# AGC.net
KiCad netlist of a schematic drawn in Altium Designer
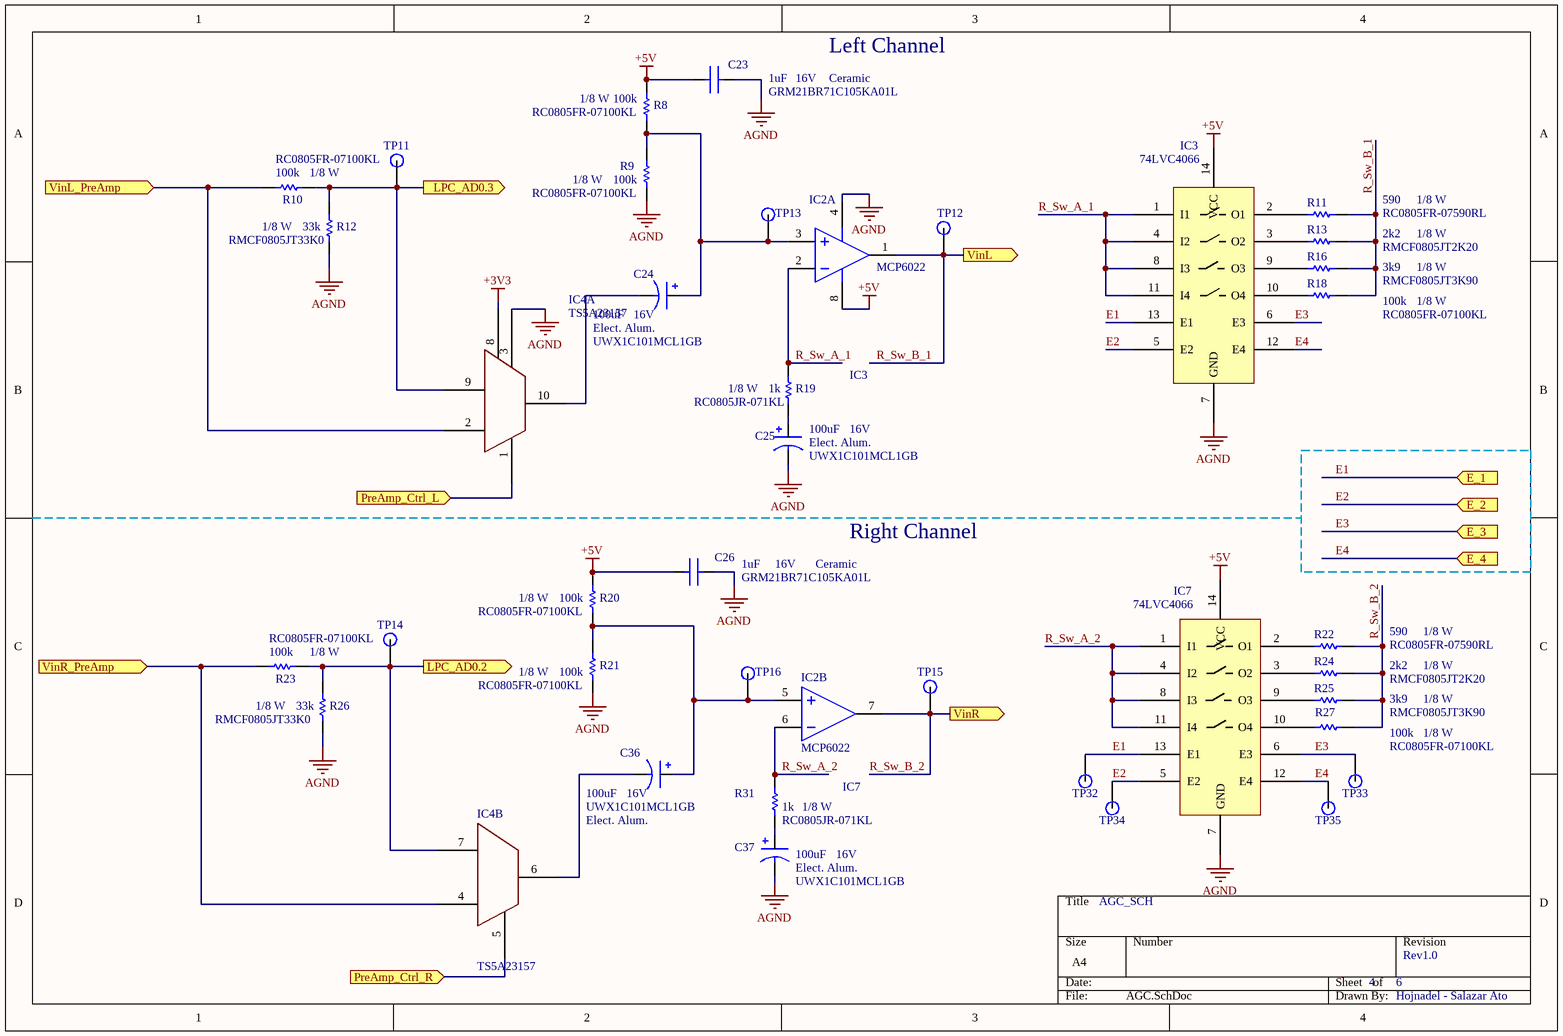
[diagram p0: AGC.SchDoc]

(export (version "E")
  (design (tool "Eeschema 10.0.6"))
  (components
    (comp (ref "C23")
      (value "1uF 16V Ceramic")
      (footprint "C_0805")
      (description "Capacitor")
      (fields
        (field (name "C") "1uF")
        (field (name "V") "16V")
        (field (name "PART NUMBER") "GRM21BR71C105KA01L")
        (field (name "MATERIAL") "Ceramic")
      )
      (libsource (lib "TDII_Lib_V2") (part "Cap1"))
    )
    (comp (ref "C24")
      (value "100uF 16V Elect. Alum.")
      (footprint "C_AE7066X54M")
      (description "Capacitor")
      (fields
        (field (name "C") "100uF")
        (field (name "V") "16V")
        (field (name "MATERIAL") "Elect. Alum.")
        (field (name "PART NUMBER") "UWX1C101MCL1GB")
      )
      (libsource (lib "TDII_Lib_V2") (part "Cap_Elec"))
    )
    (comp (ref "C25")
      (value "100uF 16V Elect. Alum.")
      (footprint "C_AE7066X54M")
      (description "Capacitor")
      (fields
        (field (name "C") "100uF")
        (field (name "V") "16V")
        (field (name "MATERIAL") "Elect. Alum.")
        (field (name "PART NUMBER") "UWX1C101MCL1GB")
      )
      (libsource (lib "") (part "Cap_Elec_1"))
    )
    (comp (ref "C26")
      (value "1uF 16V Ceramic")
      (footprint "C_0805")
      (description "Capacitor")
      (fields
        (field (name "C") "1uF")
        (field (name "V") "16V")
        (field (name "PART NUMBER") "GRM21BR71C105KA01L")
        (field (name "MATERIAL") "Ceramic")
      )
      (libsource (lib "TDII_Lib_V2") (part "Cap1"))
    )
    (comp (ref "C36")
      (value "100uF 16V Elect. Alum.")
      (footprint "C_AE7066X54M")
      (description "Capacitor")
      (fields
        (field (name "C") "100uF")
        (field (name "V") "16V")
        (field (name "MATERIAL") "Elect. Alum.")
        (field (name "PART NUMBER") "UWX1C101MCL1GB")
      )
      (libsource (lib "TDII_Lib_V2") (part "Cap_Elec"))
    )
    (comp (ref "C37")
      (value "100uF 16V Elect. Alum.")
      (footprint "C_AE7066X54M")
      (description "Capacitor")
      (fields
        (field (name "C") "100uF")
        (field (name "V") "16V")
        (field (name "MATERIAL") "Elect. Alum.")
        (field (name "PART NUMBER") "UWX1C101MCL1GB")
      )
      (libsource (lib "") (part "Cap_Elec_1"))
    )
    (comp (ref "IC2") (value "MCP6022") (footprint "SOIC_D8") (libsource (lib "LituLib") (part "OpAmp_Dual")))
    (comp (ref "IC3")
      (value "74LVC4066")
      (footprint "SO14")
      (fields (field (name "PART NUMBER") "74LVC4066BQ,115"))
      (libsource (lib "TDII_Lib_V2") (part "Q_B_Switch_2"))
    )
    (comp (ref "IC4")
      (value "TS5A23157")
      (footprint "TSSOP50P490X110-10N")
      (description "Analog Switch")
      (libsource (lib "TDII_Lib_V2") (part "A_SW_2x2{colon}1_VSSOP"))
    )
    (comp (ref "IC7")
      (value "74LVC4066")
      (footprint "SO14")
      (fields (field (name "PART NUMBER") "74LVC4066BQ,115"))
      (libsource (lib "TDII_Lib_V2") (part "Q_B_Switch_2"))
    )
    (comp (ref "R8")
      (value "100k")
      (footprint "R_0805")
      (description "Resistor")
      (fields
        (field (name "POWER") "1/8 W")
        (field (name "PART NUMBER") "RC0805FR-07100KL")
        (field (name "Comment") "100k 1/8W")
      )
      (libsource (lib "TDII_Lib_V2") (part "Res1"))
    )
    (comp (ref "R9")
      (value "100k")
      (footprint "R_0805")
      (description "Resistor")
      (fields
        (field (name "POWER") "1/8 W")
        (field (name "PART NUMBER") "RC0805FR-07100KL")
        (field (name "Comment") "100k 1/8W")
      )
      (libsource (lib "TDII_Lib_V2") (part "Res1"))
    )
    (comp (ref "R10")
      (value "100k")
      (footprint "R_0805")
      (description "Resistor")
      (fields
        (field (name "POWER") "1/8 W")
        (field (name "PART NUMBER") "RC0805FR-07100KL")
        (field (name "Comment") "100k 1/8W")
      )
      (libsource (lib "TDII_Lib_V2") (part "Res1"))
    )
    (comp (ref "R11")
      (value "590")
      (footprint "R_0805")
      (description "Resistor")
      (fields
        (field (name "POWER") "1/8 W")
        (field (name "PART NUMBER") "RC0805FR-07590RL")
        (field (name "Comment") "590 1/8W")
      )
      (libsource (lib "TDII_Lib_V2") (part "Res1"))
    )
    (comp (ref "R12")
      (value "33k")
      (footprint "R_0805")
      (description "Resistor")
      (fields
        (field (name "POWER") "1/8 W")
        (field (name "PART NUMBER") "RMCF0805JT33K0")
        (field (name "Comment") "33k 1/8W")
      )
      (libsource (lib "TDII_Lib_V2") (part "Res1"))
    )
    (comp (ref "R13")
      (value "2k2")
      (footprint "R_0805")
      (description "Resistor")
      (fields
        (field (name "POWER") "1/8 W")
        (field (name "PART NUMBER") "RMCF0805JT2K20")
        (field (name "Comment") "2k2 1/8W")
      )
      (libsource (lib "TDII_Lib_V2") (part "Res1"))
    )
    (comp (ref "R16")
      (value "3k9")
      (footprint "R_0805")
      (description "Resistor")
      (fields
        (field (name "POWER") "1/8 W")
        (field (name "PART NUMBER") "RMCF0805JT3K90")
        (field (name "Comment") "3k9 1/8W")
      )
      (libsource (lib "TDII_Lib_V2") (part "Res1"))
    )
    (comp (ref "R18")
      (value "100k")
      (footprint "R_0805")
      (description "Resistor")
      (fields
        (field (name "POWER") "1/8 W")
        (field (name "PART NUMBER") "RC0805FR-07100KL")
        (field (name "Comment") "100k 1/8W")
      )
      (libsource (lib "TDII_Lib_V2") (part "Res1"))
    )
    (comp (ref "R19")
      (value "1k")
      (footprint "R_0805")
      (description "Resistor")
      (fields
        (field (name "POWER") "1/8 W")
        (field (name "PART NUMBER") "RC0805JR-071KL")
        (field (name "Comment") "1k 1/8W")
      )
      (libsource (lib "TDII_Lib_V2") (part "Res1"))
    )
    (comp (ref "R20")
      (value "100k")
      (footprint "R_0805")
      (description "Resistor")
      (fields
        (field (name "POWER") "1/8 W")
        (field (name "PART NUMBER") "RC0805FR-07100KL")
        (field (name "Comment") "100k 1/8W")
      )
      (libsource (lib "TDII_Lib_V2") (part "Res1"))
    )
    (comp (ref "R21")
      (value "100k")
      (footprint "R_0805")
      (description "Resistor")
      (fields
        (field (name "POWER") "1/8 W")
        (field (name "PART NUMBER") "RC0805FR-07100KL")
        (field (name "Comment") "100k 1/8W")
      )
      (libsource (lib "TDII_Lib_V2") (part "Res1"))
    )
    (comp (ref "R22")
      (value "590")
      (footprint "R_0805")
      (description "Resistor")
      (fields
        (field (name "POWER") "1/8 W")
        (field (name "PART NUMBER") "RC0805FR-07590RL")
        (field (name "Comment") "590 1/8W")
      )
      (libsource (lib "TDII_Lib_V2") (part "Res1"))
    )
    (comp (ref "R23")
      (value "100k")
      (footprint "R_0805")
      (description "Resistor")
      (fields
        (field (name "POWER") "1/8 W")
        (field (name "PART NUMBER") "RC0805FR-07100KL")
        (field (name "Comment") "100k 1/8W")
      )
      (libsource (lib "TDII_Lib_V2") (part "Res1"))
    )
    (comp (ref "R24")
      (value "2k2")
      (footprint "R_0805")
      (description "Resistor")
      (fields
        (field (name "POWER") "1/8 W")
        (field (name "PART NUMBER") "RMCF0805JT2K20")
        (field (name "Comment") "2k2 1/8W")
      )
      (libsource (lib "TDII_Lib_V2") (part "Res1"))
    )
    (comp (ref "R25")
      (value "3k9")
      (footprint "R_0805")
      (description "Resistor")
      (fields
        (field (name "POWER") "1/8 W")
        (field (name "PART NUMBER") "RMCF0805JT3K90")
        (field (name "Comment") "3k9 1/8W")
      )
      (libsource (lib "TDII_Lib_V2") (part "Res1"))
    )
    (comp (ref "R26")
      (value "33k")
      (footprint "R_0805")
      (description "Resistor")
      (fields
        (field (name "POWER") "1/8 W")
        (field (name "PART NUMBER") "RMCF0805JT33K0")
        (field (name "Comment") "33k 1/8W")
      )
      (libsource (lib "TDII_Lib_V2") (part "Res1"))
    )
    (comp (ref "R27")
      (value "100k")
      (footprint "R_0805")
      (description "Resistor")
      (fields
        (field (name "POWER") "1/8 W")
        (field (name "PART NUMBER") "RC0805FR-07100KL")
        (field (name "Comment") "100k 1/8W")
      )
      (libsource (lib "TDII_Lib_V2") (part "Res1"))
    )
    (comp (ref "R31")
      (value "1k")
      (footprint "R_0805")
      (description "Resistor")
      (fields
        (field (name "POWER") "1/8 W")
        (field (name "PART NUMBER") "RC0805JR-071KL")
        (field (name "Comment") "1k 1/8W")
      )
      (libsource (lib "TDII_Lib_V2") (part "Res1"))
    )
    (comp (ref "TP11")
      (value "TP")
      (footprint "TP")
      (description "Test Point")
      (libsource (lib "LituLib") (part "Test Point"))
    )
    (comp (ref "TP12")
      (value "TP")
      (footprint "TP")
      (description "Test Point")
      (libsource (lib "LituLib") (part "Test Point"))
    )
    (comp (ref "TP13")
      (value "TP")
      (footprint "TP")
      (description "Test Point")
      (libsource (lib "LituLib") (part "Test Point"))
    )
    (comp (ref "TP14")
      (value "TP")
      (footprint "TP")
      (description "Test Point")
      (libsource (lib "LituLib") (part "Test Point"))
    )
    (comp (ref "TP15")
      (value "TP")
      (footprint "TP")
      (description "Test Point")
      (libsource (lib "LituLib") (part "Test Point"))
    )
    (comp (ref "TP16")
      (value "TP")
      (footprint "TP")
      (description "Test Point")
      (libsource (lib "LituLib") (part "Test Point"))
    )
    (comp (ref "TP32")
      (value "TP")
      (footprint "TP")
      (description "Test Point")
      (libsource (lib "LituLib") (part "Test Point"))
    )
    (comp (ref "TP33")
      (value "TP")
      (footprint "TP")
      (description "Test Point")
      (libsource (lib "LituLib") (part "Test Point"))
    )
    (comp (ref "TP34")
      (value "TP")
      (footprint "TP")
      (description "Test Point")
      (libsource (lib "LituLib") (part "Test Point"))
    )
    (comp (ref "TP35")
      (value "TP")
      (footprint "TP")
      (description "Test Point")
      (libsource (lib "LituLib") (part "Test Point"))
    )
  )
  (nets
    (net (code "1") (name "+3V3") (class "Default")
      (node (ref "IC4") (pin "8") (pinfunction "VDD_8") (pintype "passive"))
    )
    (net (code "2") (name "+5V") (class "Default")
      (node (ref "C23") (pin "1") (pinfunction "1_1") (pintype "passive"))
      (node (ref "C26") (pin "1") (pinfunction "1_1") (pintype "passive"))
      (node (ref "IC2") (pin "8") (pinfunction "VDD_8") (pintype "power_in"))
      (node (ref "IC3") (pin "14") (pinfunction "VCC_14") (pintype "passive"))
      (node (ref "IC7") (pin "14") (pinfunction "VCC_14") (pintype "passive"))
      (node (ref "R20") (pin "2") (pinfunction "2_2") (pintype "passive"))
      (node (ref "R8") (pin "2") (pinfunction "2_2") (pintype "passive"))
    )
    (net (code "3") (name "/E1") (class "Default")
      (node (ref "IC3") (pin "13") (pinfunction "E1_13") (pintype "passive"))
      (node (ref "IC7") (pin "13") (pinfunction "E1_13") (pintype "passive"))
      (node (ref "TP32") (pin "1") (pinfunction "1_1") (pintype "passive"))
    )
    (net (code "4") (name "/E2") (class "Default")
      (node (ref "IC3") (pin "5") (pinfunction "E2_5") (pintype "passive"))
      (node (ref "IC7") (pin "5") (pinfunction "E2_5") (pintype "passive"))
      (node (ref "TP34") (pin "1") (pinfunction "1_1") (pintype "passive"))
    )
    (net (code "5") (name "/E3") (class "Default")
      (node (ref "IC3") (pin "6") (pinfunction "E3_6") (pintype "passive"))
      (node (ref "IC7") (pin "6") (pinfunction "E3_6") (pintype "passive"))
      (node (ref "TP33") (pin "1") (pinfunction "1_1") (pintype "passive"))
    )
    (net (code "6") (name "/E4") (class "Default")
      (node (ref "IC3") (pin "12") (pinfunction "E4_12") (pintype "passive"))
      (node (ref "IC7") (pin "12") (pinfunction "E4_12") (pintype "passive"))
      (node (ref "TP35") (pin "1") (pinfunction "1_1") (pintype "passive"))
    )
    (net (code "7") (name "/LPC_AD0.2") (class "Default")
      (node (ref "IC4") (pin "7") (pinfunction "NC2_7") (pintype "passive"))
      (node (ref "R23") (pin "2") (pinfunction "2_2") (pintype "passive"))
      (node (ref "R26") (pin "1") (pinfunction "1_1") (pintype "passive"))
      (node (ref "TP14") (pin "1") (pinfunction "1_1") (pintype "passive"))
    )
    (net (code "8") (name "/LPC_AD0.3") (class "Default")
      (node (ref "IC4") (pin "9") (pinfunction "NC1_9") (pintype "passive"))
      (node (ref "R10") (pin "2") (pinfunction "2_2") (pintype "passive"))
      (node (ref "R12") (pin "1") (pinfunction "1_1") (pintype "passive"))
      (node (ref "TP11") (pin "1") (pinfunction "1_1") (pintype "passive"))
    )
    (net (code "9") (name "/PreAmp_Ctrl_L") (class "Default")
      (node (ref "IC4") (pin "1") (pinfunction "IN1_1") (pintype "passive"))
    )
    (net (code "10") (name "/PreAmp_Ctrl_R") (class "Default")
      (node (ref "IC4") (pin "5") (pinfunction "IN2_5") (pintype "passive"))
    )
    (net (code "11") (name "/R_Sw_A_1") (class "Default")
      (node (ref "IC2") (pin "2") (pinfunction "IN-_2") (pintype "passive"))
      (node (ref "IC3") (pin "1") (pinfunction "I1_1") (pintype "passive"))
      (node (ref "IC3") (pin "11") (pinfunction "I4_11") (pintype "passive"))
      (node (ref "IC3") (pin "4") (pinfunction "I2_4") (pintype "passive"))
      (node (ref "IC3") (pin "8") (pinfunction "I3_8") (pintype "passive"))
      (node (ref "R19") (pin "1") (pinfunction "1_1") (pintype "passive"))
    )
    (net (code "12") (name "/R_Sw_A_2") (class "Default")
      (node (ref "IC2") (pin "6") (pinfunction "IN-_6") (pintype "passive"))
      (node (ref "IC7") (pin "1") (pinfunction "I1_1") (pintype "passive"))
      (node (ref "IC7") (pin "11") (pinfunction "I4_11") (pintype "passive"))
      (node (ref "IC7") (pin "4") (pinfunction "I2_4") (pintype "passive"))
      (node (ref "IC7") (pin "8") (pinfunction "I3_8") (pintype "passive"))
      (node (ref "R31") (pin "1") (pinfunction "1_1") (pintype "passive"))
    )
    (net (code "13") (name "/R_Sw_B_1") (class "Default")
      (node (ref "IC2") (pin "1") (pinfunction "OUT_1") (pintype "passive"))
      (node (ref "R11") (pin "1") (pinfunction "1_1") (pintype "passive"))
      (node (ref "R13") (pin "1") (pinfunction "1_1") (pintype "passive"))
      (node (ref "R16") (pin "1") (pinfunction "1_1") (pintype "passive"))
      (node (ref "R18") (pin "1") (pinfunction "1_1") (pintype "passive"))
      (node (ref "TP12") (pin "1") (pinfunction "1_1") (pintype "passive"))
    )
    (net (code "14") (name "/R_Sw_B_2") (class "Default")
      (node (ref "IC2") (pin "7") (pinfunction "OUT_7") (pintype "passive"))
      (node (ref "R22") (pin "1") (pinfunction "1_1") (pintype "passive"))
      (node (ref "R24") (pin "1") (pinfunction "1_1") (pintype "passive"))
      (node (ref "R25") (pin "1") (pinfunction "1_1") (pintype "passive"))
      (node (ref "R27") (pin "1") (pinfunction "1_1") (pintype "passive"))
      (node (ref "TP15") (pin "1") (pinfunction "1_1") (pintype "passive"))
    )
    (net (code "15") (name "/VinL_PreAmp") (class "Default")
      (node (ref "IC4") (pin "2") (pinfunction "NO1_2") (pintype "passive"))
      (node (ref "R10") (pin "1") (pinfunction "1_1") (pintype "passive"))
    )
    (net (code "16") (name "/VinR_PreAmp") (class "Default")
      (node (ref "IC4") (pin "4") (pinfunction "NO2_4") (pintype "passive"))
      (node (ref "R23") (pin "1") (pinfunction "1_1") (pintype "passive"))
    )
    (net (code "17") (name "AGND") (class "Default")
      (node (ref "C23") (pin "2") (pinfunction "2_2") (pintype "passive"))
      (node (ref "C25") (pin "2") (pinfunction "2_2") (pintype "passive"))
      (node (ref "C26") (pin "2") (pinfunction "2_2") (pintype "passive"))
      (node (ref "C37") (pin "2") (pinfunction "2_2") (pintype "passive"))
      (node (ref "IC2") (pin "4") (pinfunction "VSS_4") (pintype "power_in"))
      (node (ref "IC3") (pin "7") (pinfunction "GND_7") (pintype "passive"))
      (node (ref "IC4") (pin "3") (pinfunction "DGND_3") (pintype "passive"))
      (node (ref "IC7") (pin "7") (pinfunction "GND_7") (pintype "passive"))
      (node (ref "R12") (pin "2") (pinfunction "2_2") (pintype "passive"))
      (node (ref "R21") (pin "1") (pinfunction "1_1") (pintype "passive"))
      (node (ref "R26") (pin "2") (pinfunction "2_2") (pintype "passive"))
      (node (ref "R9") (pin "1") (pinfunction "1_1") (pintype "passive"))
    )
    (net (code "18") (name "Net-(C25-Pad1)") (class "Default")
      (node (ref "C25") (pin "1") (pinfunction "1_1") (pintype "passive"))
      (node (ref "R19") (pin "2") (pinfunction "2_2") (pintype "passive"))
    )
    (net (code "19") (name "Net-(C37-Pad1)") (class "Default")
      (node (ref "C37") (pin "1") (pinfunction "1_1") (pintype "passive"))
      (node (ref "R31") (pin "2") (pinfunction "2_2") (pintype "passive"))
    )
    (net (code "20") (name "Net-(IC2A-IN+)") (class "Default")
      (node (ref "C24") (pin "1") (pinfunction "1_1") (pintype "passive"))
      (node (ref "IC2") (pin "3") (pinfunction "IN+_3") (pintype "passive"))
      (node (ref "R8") (pin "1") (pinfunction "1_1") (pintype "passive"))
      (node (ref "R9") (pin "2") (pinfunction "2_2") (pintype "passive"))
      (node (ref "TP13") (pin "1") (pinfunction "1_1") (pintype "passive"))
    )
    (net (code "21") (name "Net-(IC2B-IN+)") (class "Default")
      (node (ref "C36") (pin "1") (pinfunction "1_1") (pintype "passive"))
      (node (ref "IC2") (pin "5") (pinfunction "IN+_5") (pintype "passive"))
      (node (ref "R20") (pin "1") (pinfunction "1_1") (pintype "passive"))
      (node (ref "R21") (pin "2") (pinfunction "2_2") (pintype "passive"))
      (node (ref "TP16") (pin "1") (pinfunction "1_1") (pintype "passive"))
    )
    (net (code "22") (name "Net-(IC3-O1)") (class "Default")
      (node (ref "IC3") (pin "2") (pinfunction "O1_2") (pintype "passive"))
      (node (ref "R11") (pin "2") (pinfunction "2_2") (pintype "passive"))
    )
    (net (code "23") (name "Net-(IC3-O2)") (class "Default")
      (node (ref "IC3") (pin "3") (pinfunction "O2_3") (pintype "passive"))
      (node (ref "R13") (pin "2") (pinfunction "2_2") (pintype "passive"))
    )
    (net (code "24") (name "Net-(IC3-O3)") (class "Default")
      (node (ref "IC3") (pin "9") (pinfunction "O3_9") (pintype "passive"))
      (node (ref "R16") (pin "2") (pinfunction "2_2") (pintype "passive"))
    )
    (net (code "25") (name "Net-(IC3-O4)") (class "Default")
      (node (ref "IC3") (pin "10") (pinfunction "O4_10") (pintype "passive"))
      (node (ref "R18") (pin "2") (pinfunction "2_2") (pintype "passive"))
    )
    (net (code "26") (name "Net-(IC4A-COM1)") (class "Default")
      (node (ref "C24") (pin "2") (pinfunction "2_2") (pintype "passive"))
      (node (ref "IC4") (pin "10") (pinfunction "COM1_10") (pintype "passive"))
    )
    (net (code "27") (name "Net-(IC4B-COM2)") (class "Default")
      (node (ref "C36") (pin "2") (pinfunction "2_2") (pintype "passive"))
      (node (ref "IC4") (pin "6") (pinfunction "COM2_6") (pintype "passive"))
    )
    (net (code "28") (name "Net-(IC7-O1)") (class "Default")
      (node (ref "IC7") (pin "2") (pinfunction "O1_2") (pintype "passive"))
      (node (ref "R22") (pin "2") (pinfunction "2_2") (pintype "passive"))
    )
    (net (code "29") (name "Net-(IC7-O2)") (class "Default")
      (node (ref "IC7") (pin "3") (pinfunction "O2_3") (pintype "passive"))
      (node (ref "R24") (pin "2") (pinfunction "2_2") (pintype "passive"))
    )
    (net (code "30") (name "Net-(IC7-O3)") (class "Default")
      (node (ref "IC7") (pin "9") (pinfunction "O3_9") (pintype "passive"))
      (node (ref "R25") (pin "2") (pinfunction "2_2") (pintype "passive"))
    )
    (net (code "31") (name "Net-(IC7-O4)") (class "Default")
      (node (ref "IC7") (pin "10") (pinfunction "O4_10") (pintype "passive"))
      (node (ref "R27") (pin "2") (pinfunction "2_2") (pintype "passive"))
    )
  )
)
